# connect.net
KiCad netlist of a schematic drawn in Altium Designer
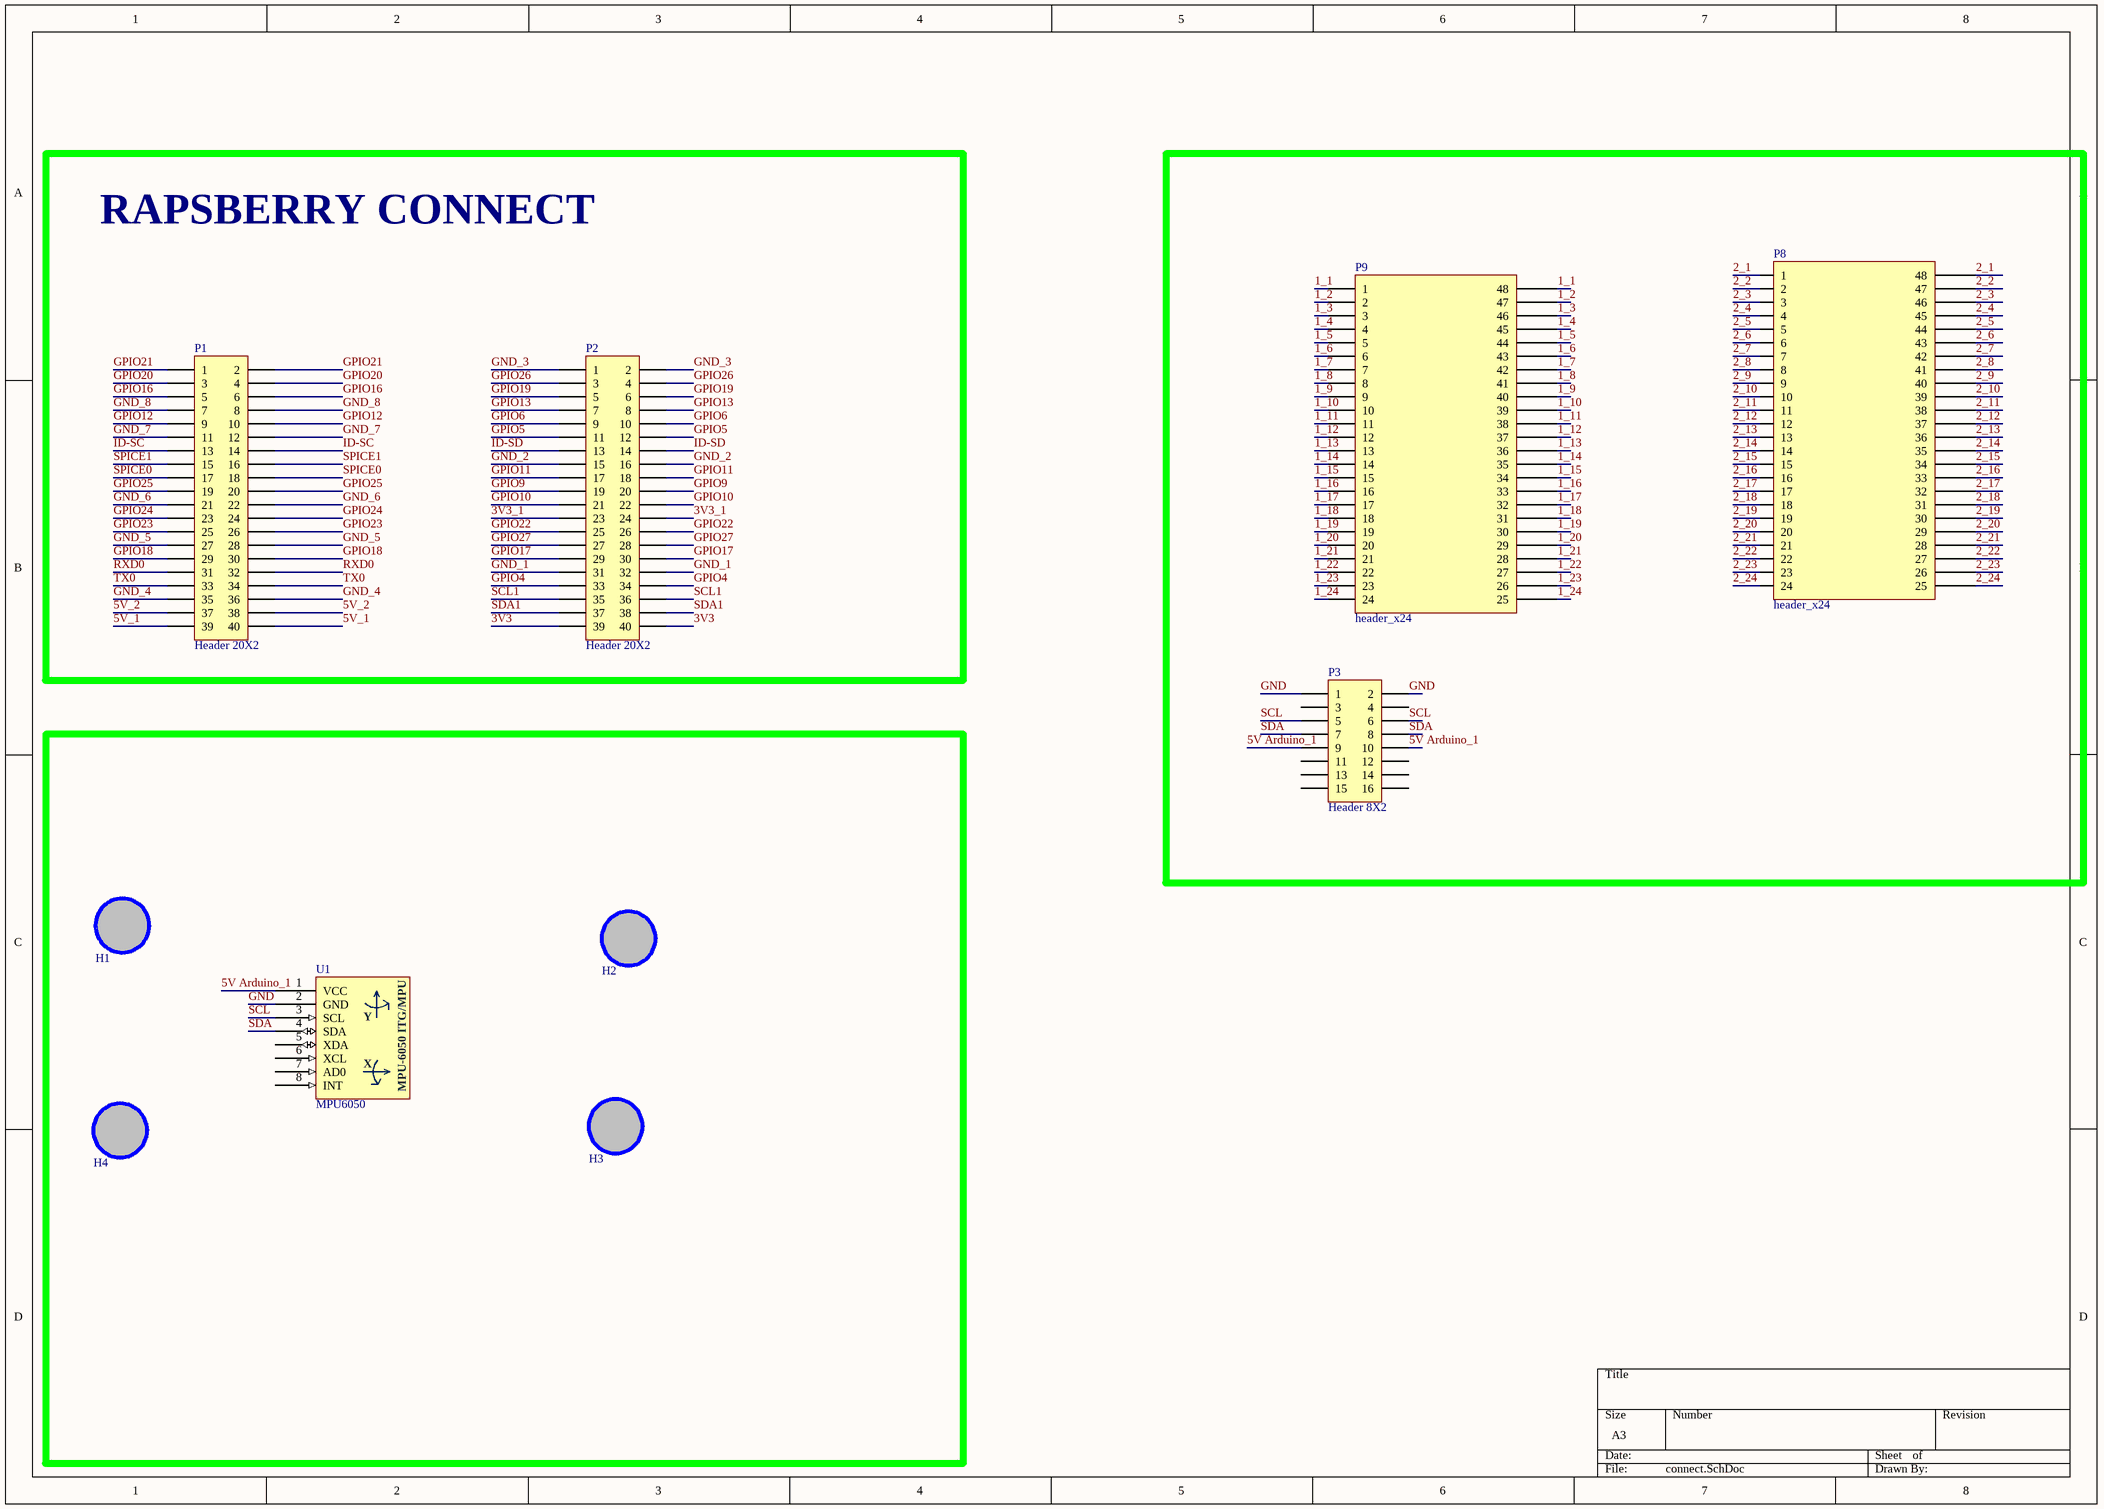
[diagram p0: connect.SchDoc]

(export (version "E")
  (design (tool "Eeschema 10.0.6"))
  (components
    (comp (ref "H1")
      (value "Hole")
      (footprint "LO KHOAN 3MM")
      (description "Hole 3mm")
      (libsource (lib "Board_C24") (part "Hole"))
    )
    (comp (ref "H2")
      (value "Hole")
      (footprint "LO KHOAN 3MM")
      (description "Hole 3mm")
      (libsource (lib "Board_C24") (part "Hole"))
    )
    (comp (ref "H3")
      (value "Hole")
      (footprint "LO KHOAN 3MM")
      (description "Hole 3mm")
      (libsource (lib "Board_C24") (part "Hole"))
    )
    (comp (ref "H4")
      (value "Hole")
      (footprint "LO KHOAN 3MM")
      (description "Hole 3mm")
      (libsource (lib "Board_C24") (part "Hole"))
    )
    (comp (ref "P1")
      (value "Header 20X2")
      (footprint "MY_2X20")
      (description "Header, 40-Pin, Dual row")
      (fields (field (name "ASID PART NUMBER") "Header 20X2-AS"))
      (libsource (lib "Mylib+Rev+4") (part "Header 20X2"))
    )
    (comp (ref "P2")
      (value "Header 20X2")
      (footprint "MY_2X20")
      (description "Header, 40-Pin, Dual row")
      (fields (field (name "ASID PART NUMBER") "Header 20X2-AS"))
      (libsource (lib "Mylib+Rev+4") (part "Header 20X2"))
    )
    (comp (ref "P3")
      (value "Header 8X2")
      (footprint "HDR/Header/16/DL")
      (description "Header, 8-Pin, Dual row")
      (libsource (lib "connectors") (part "Header 8X2"))
    )
    (comp (ref "P8")
      (value "header_x24")
      (footprint "header_x24")
      (libsource (lib "Integrated_Library1") (part "header_x24"))
    )
    (comp (ref "P9")
      (value "header_x24")
      (footprint "header_x24")
      (libsource (lib "Integrated_Library1") (part "header_x24"))
    )
    (comp (ref "U1")
      (value "MPU6050")
      (footprint "MPU-6050")
      (fields (field (name "MFR") "DFRobot") (field (name "UTILIZED IC / PART") "MPU-6050"))
      (libsource (lib "Board_C24") (part "MPU6050"))
    )
  )
  (nets
    (net (code "1") (name "/1_1") (class "Default")
      (node (ref "P9") (pin "1") (pinfunction "1_1") (pintype "passive"))
      (node (ref "P9") (pin "48") (pinfunction "48_48") (pintype "passive"))
    )
    (net (code "2") (name "/1_2") (class "Default")
      (node (ref "P9") (pin "2") (pinfunction "2_2") (pintype "passive"))
      (node (ref "P9") (pin "47") (pinfunction "47_47") (pintype "passive"))
    )
    (net (code "3") (name "/1_3") (class "Default")
      (node (ref "P9") (pin "3") (pinfunction "3_3") (pintype "passive"))
      (node (ref "P9") (pin "46") (pinfunction "46_46") (pintype "passive"))
    )
    (net (code "4") (name "/1_4") (class "Default")
      (node (ref "P9") (pin "4") (pinfunction "4_4") (pintype "passive"))
      (node (ref "P9") (pin "45") (pinfunction "45_45") (pintype "passive"))
    )
    (net (code "5") (name "/1_5") (class "Default")
      (node (ref "P9") (pin "44") (pinfunction "44_44") (pintype "passive"))
      (node (ref "P9") (pin "5") (pinfunction "5_5") (pintype "passive"))
    )
    (net (code "6") (name "/1_6") (class "Default")
      (node (ref "P9") (pin "43") (pinfunction "43_43") (pintype "passive"))
      (node (ref "P9") (pin "6") (pinfunction "6_6") (pintype "passive"))
    )
    (net (code "7") (name "/1_7") (class "Default")
      (node (ref "P9") (pin "42") (pinfunction "42_42") (pintype "passive"))
      (node (ref "P9") (pin "7") (pinfunction "7_7") (pintype "passive"))
    )
    (net (code "8") (name "/1_8") (class "Default")
      (node (ref "P9") (pin "41") (pinfunction "41_41") (pintype "passive"))
      (node (ref "P9") (pin "8") (pinfunction "8_8") (pintype "passive"))
    )
    (net (code "9") (name "/1_9") (class "Default")
      (node (ref "P9") (pin "40") (pinfunction "40_40") (pintype "passive"))
      (node (ref "P9") (pin "9") (pinfunction "9_9") (pintype "passive"))
    )
    (net (code "10") (name "/1_10") (class "Default")
      (node (ref "P9") (pin "10") (pinfunction "10_10") (pintype "passive"))
      (node (ref "P9") (pin "39") (pinfunction "39_39") (pintype "passive"))
    )
    (net (code "11") (name "/1_11") (class "Default")
      (node (ref "P9") (pin "11") (pinfunction "11_11") (pintype "passive"))
      (node (ref "P9") (pin "38") (pinfunction "38_38") (pintype "passive"))
    )
    (net (code "12") (name "/1_12") (class "Default")
      (node (ref "P9") (pin "12") (pinfunction "12_12") (pintype "passive"))
      (node (ref "P9") (pin "37") (pinfunction "37_37") (pintype "passive"))
    )
    (net (code "13") (name "/1_13") (class "Default")
      (node (ref "P9") (pin "13") (pinfunction "13_13") (pintype "passive"))
      (node (ref "P9") (pin "36") (pinfunction "36_36") (pintype "passive"))
    )
    (net (code "14") (name "/1_14") (class "Default")
      (node (ref "P9") (pin "14") (pinfunction "14_14") (pintype "passive"))
      (node (ref "P9") (pin "35") (pinfunction "35_35") (pintype "passive"))
    )
    (net (code "15") (name "/1_15") (class "Default")
      (node (ref "P9") (pin "15") (pinfunction "15_15") (pintype "passive"))
      (node (ref "P9") (pin "34") (pinfunction "34_34") (pintype "passive"))
    )
    (net (code "16") (name "/1_16") (class "Default")
      (node (ref "P9") (pin "16") (pinfunction "16_16") (pintype "passive"))
      (node (ref "P9") (pin "33") (pinfunction "33_33") (pintype "passive"))
    )
    (net (code "17") (name "/1_17") (class "Default")
      (node (ref "P9") (pin "17") (pinfunction "17_17") (pintype "passive"))
      (node (ref "P9") (pin "32") (pinfunction "32_32") (pintype "passive"))
    )
    (net (code "18") (name "/1_18") (class "Default")
      (node (ref "P9") (pin "18") (pinfunction "18_18") (pintype "passive"))
      (node (ref "P9") (pin "31") (pinfunction "31_31") (pintype "passive"))
    )
    (net (code "19") (name "/1_19") (class "Default")
      (node (ref "P9") (pin "19") (pinfunction "19_19") (pintype "passive"))
      (node (ref "P9") (pin "30") (pinfunction "30_30") (pintype "passive"))
    )
    (net (code "20") (name "/1_20") (class "Default")
      (node (ref "P9") (pin "20") (pinfunction "20_20") (pintype "passive"))
      (node (ref "P9") (pin "29") (pinfunction "29_29") (pintype "passive"))
    )
    (net (code "21") (name "/1_21") (class "Default")
      (node (ref "P9") (pin "21") (pinfunction "21_21") (pintype "passive"))
      (node (ref "P9") (pin "28") (pinfunction "28_28") (pintype "passive"))
    )
    (net (code "22") (name "/1_22") (class "Default")
      (node (ref "P9") (pin "22") (pinfunction "22_22") (pintype "passive"))
      (node (ref "P9") (pin "27") (pinfunction "27_27") (pintype "passive"))
    )
    (net (code "23") (name "/1_23") (class "Default")
      (node (ref "P9") (pin "23") (pinfunction "23_23") (pintype "passive"))
      (node (ref "P9") (pin "26") (pinfunction "26_26") (pintype "passive"))
    )
    (net (code "24") (name "/1_24") (class "Default")
      (node (ref "P9") (pin "24") (pinfunction "24_24") (pintype "passive"))
      (node (ref "P9") (pin "25") (pinfunction "25_25") (pintype "passive"))
    )
    (net (code "25") (name "/2_1") (class "Default")
      (node (ref "P8") (pin "1") (pinfunction "1_1") (pintype "passive"))
      (node (ref "P8") (pin "48") (pinfunction "48_48") (pintype "passive"))
    )
    (net (code "26") (name "/2_2") (class "Default")
      (node (ref "P8") (pin "2") (pinfunction "2_2") (pintype "passive"))
      (node (ref "P8") (pin "47") (pinfunction "47_47") (pintype "passive"))
    )
    (net (code "27") (name "/2_3") (class "Default")
      (node (ref "P8") (pin "3") (pinfunction "3_3") (pintype "passive"))
      (node (ref "P8") (pin "46") (pinfunction "46_46") (pintype "passive"))
    )
    (net (code "28") (name "/2_4") (class "Default")
      (node (ref "P8") (pin "4") (pinfunction "4_4") (pintype "passive"))
      (node (ref "P8") (pin "45") (pinfunction "45_45") (pintype "passive"))
    )
    (net (code "29") (name "/2_5") (class "Default")
      (node (ref "P8") (pin "44") (pinfunction "44_44") (pintype "passive"))
      (node (ref "P8") (pin "5") (pinfunction "5_5") (pintype "passive"))
    )
    (net (code "30") (name "/2_6") (class "Default")
      (node (ref "P8") (pin "43") (pinfunction "43_43") (pintype "passive"))
      (node (ref "P8") (pin "6") (pinfunction "6_6") (pintype "passive"))
    )
    (net (code "31") (name "/2_7") (class "Default")
      (node (ref "P8") (pin "42") (pinfunction "42_42") (pintype "passive"))
      (node (ref "P8") (pin "7") (pinfunction "7_7") (pintype "passive"))
    )
    (net (code "32") (name "/2_8") (class "Default")
      (node (ref "P8") (pin "41") (pinfunction "41_41") (pintype "passive"))
      (node (ref "P8") (pin "8") (pinfunction "8_8") (pintype "passive"))
    )
    (net (code "33") (name "/2_9") (class "Default")
      (node (ref "P8") (pin "40") (pinfunction "40_40") (pintype "passive"))
      (node (ref "P8") (pin "9") (pinfunction "9_9") (pintype "passive"))
    )
    (net (code "34") (name "/2_10") (class "Default")
      (node (ref "P8") (pin "10") (pinfunction "10_10") (pintype "passive"))
      (node (ref "P8") (pin "39") (pinfunction "39_39") (pintype "passive"))
    )
    (net (code "35") (name "/2_11") (class "Default")
      (node (ref "P8") (pin "11") (pinfunction "11_11") (pintype "passive"))
      (node (ref "P8") (pin "38") (pinfunction "38_38") (pintype "passive"))
    )
    (net (code "36") (name "/2_12") (class "Default")
      (node (ref "P8") (pin "12") (pinfunction "12_12") (pintype "passive"))
      (node (ref "P8") (pin "37") (pinfunction "37_37") (pintype "passive"))
    )
    (net (code "37") (name "/2_13") (class "Default")
      (node (ref "P8") (pin "13") (pinfunction "13_13") (pintype "passive"))
      (node (ref "P8") (pin "36") (pinfunction "36_36") (pintype "passive"))
    )
    (net (code "38") (name "/2_14") (class "Default")
      (node (ref "P8") (pin "14") (pinfunction "14_14") (pintype "passive"))
      (node (ref "P8") (pin "35") (pinfunction "35_35") (pintype "passive"))
    )
    (net (code "39") (name "/2_15") (class "Default")
      (node (ref "P8") (pin "15") (pinfunction "15_15") (pintype "passive"))
      (node (ref "P8") (pin "34") (pinfunction "34_34") (pintype "passive"))
    )
    (net (code "40") (name "/2_16") (class "Default")
      (node (ref "P8") (pin "16") (pinfunction "16_16") (pintype "passive"))
      (node (ref "P8") (pin "33") (pinfunction "33_33") (pintype "passive"))
    )
    (net (code "41") (name "/2_17") (class "Default")
      (node (ref "P8") (pin "17") (pinfunction "17_17") (pintype "passive"))
      (node (ref "P8") (pin "32") (pinfunction "32_32") (pintype "passive"))
    )
    (net (code "42") (name "/2_18") (class "Default")
      (node (ref "P8") (pin "18") (pinfunction "18_18") (pintype "passive"))
      (node (ref "P8") (pin "31") (pinfunction "31_31") (pintype "passive"))
    )
    (net (code "43") (name "/2_19") (class "Default")
      (node (ref "P8") (pin "19") (pinfunction "19_19") (pintype "passive"))
      (node (ref "P8") (pin "30") (pinfunction "30_30") (pintype "passive"))
    )
    (net (code "44") (name "/2_20") (class "Default")
      (node (ref "P8") (pin "20") (pinfunction "20_20") (pintype "passive"))
      (node (ref "P8") (pin "29") (pinfunction "29_29") (pintype "passive"))
    )
    (net (code "45") (name "/2_21") (class "Default")
      (node (ref "P8") (pin "21") (pinfunction "21_21") (pintype "passive"))
      (node (ref "P8") (pin "28") (pinfunction "28_28") (pintype "passive"))
    )
    (net (code "46") (name "/2_22") (class "Default")
      (node (ref "P8") (pin "22") (pinfunction "22_22") (pintype "passive"))
      (node (ref "P8") (pin "27") (pinfunction "27_27") (pintype "passive"))
    )
    (net (code "47") (name "/2_23") (class "Default")
      (node (ref "P8") (pin "23") (pinfunction "23_23") (pintype "passive"))
      (node (ref "P8") (pin "26") (pinfunction "26_26") (pintype "passive"))
    )
    (net (code "48") (name "/2_24") (class "Default")
      (node (ref "P8") (pin "24") (pinfunction "24_24") (pintype "passive"))
      (node (ref "P8") (pin "25") (pinfunction "25_25") (pintype "passive"))
    )
    (net (code "49") (name "/3V3") (class "Default")
      (node (ref "P2") (pin "39") (pinfunction "39_39") (pintype "passive"))
      (node (ref "P2") (pin "40") (pinfunction "40_40") (pintype "passive"))
    )
    (net (code "50") (name "/3V3_1") (class "Default")
      (node (ref "P2") (pin "23") (pinfunction "23_23") (pintype "passive"))
      (node (ref "P2") (pin "24") (pinfunction "24_24") (pintype "passive"))
    )
    (net (code "51") (name "/5V Arduino_1") (class "Default")
      (node (ref "P3") (pin "10") (pinfunction "10_10") (pintype "passive"))
      (node (ref "P3") (pin "9") (pinfunction "9_9") (pintype "passive"))
      (node (ref "U1") (pin "1") (pinfunction "VCC_1") (pintype "power_in"))
    )
    (net (code "52") (name "/5V_1") (class "Default")
      (node (ref "P1") (pin "39") (pinfunction "39_39") (pintype "passive"))
      (node (ref "P1") (pin "40") (pinfunction "40_40") (pintype "passive"))
    )
    (net (code "53") (name "/5V_2") (class "Default")
      (node (ref "P1") (pin "37") (pinfunction "37_37") (pintype "passive"))
      (node (ref "P1") (pin "38") (pinfunction "38_38") (pintype "passive"))
    )
    (net (code "54") (name "/GND") (class "Default")
      (node (ref "P3") (pin "1") (pinfunction "1_1") (pintype "passive"))
      (node (ref "P3") (pin "2") (pinfunction "2_2") (pintype "passive"))
      (node (ref "U1") (pin "2") (pinfunction "GND_2") (pintype "power_in"))
    )
    (net (code "55") (name "/GND_1") (class "Default")
      (node (ref "P2") (pin "31") (pinfunction "31_31") (pintype "passive"))
      (node (ref "P2") (pin "32") (pinfunction "32_32") (pintype "passive"))
    )
    (net (code "56") (name "/GND_2") (class "Default")
      (node (ref "P2") (pin "15") (pinfunction "15_15") (pintype "passive"))
      (node (ref "P2") (pin "16") (pinfunction "16_16") (pintype "passive"))
    )
    (net (code "57") (name "/GND_3") (class "Default")
      (node (ref "P2") (pin "1") (pinfunction "1_1") (pintype "passive"))
      (node (ref "P2") (pin "2") (pinfunction "2_2") (pintype "passive"))
    )
    (net (code "58") (name "/GND_4") (class "Default")
      (node (ref "P1") (pin "35") (pinfunction "35_35") (pintype "passive"))
      (node (ref "P1") (pin "36") (pinfunction "36_36") (pintype "passive"))
    )
    (net (code "59") (name "/GND_5") (class "Default")
      (node (ref "P1") (pin "27") (pinfunction "27_27") (pintype "passive"))
      (node (ref "P1") (pin "28") (pinfunction "28_28") (pintype "passive"))
    )
    (net (code "60") (name "/GND_6") (class "Default")
      (node (ref "P1") (pin "21") (pinfunction "21_21") (pintype "passive"))
      (node (ref "P1") (pin "22") (pinfunction "22_22") (pintype "passive"))
    )
    (net (code "61") (name "/GND_7") (class "Default")
      (node (ref "P1") (pin "11") (pinfunction "11_11") (pintype "passive"))
      (node (ref "P1") (pin "12") (pinfunction "12_12") (pintype "passive"))
    )
    (net (code "62") (name "/GND_8") (class "Default")
      (node (ref "P1") (pin "7") (pinfunction "7_7") (pintype "passive"))
      (node (ref "P1") (pin "8") (pinfunction "8_8") (pintype "passive"))
    )
    (net (code "63") (name "/GPIO4") (class "Default")
      (node (ref "P2") (pin "33") (pinfunction "33_33") (pintype "passive"))
      (node (ref "P2") (pin "34") (pinfunction "34_34") (pintype "passive"))
    )
    (net (code "64") (name "/GPIO5") (class "Default")
      (node (ref "P2") (pin "11") (pinfunction "11_11") (pintype "passive"))
      (node (ref "P2") (pin "12") (pinfunction "12_12") (pintype "passive"))
    )
    (net (code "65") (name "/GPIO6") (class "Default")
      (node (ref "P2") (pin "10") (pinfunction "10_10") (pintype "passive"))
      (node (ref "P2") (pin "9") (pinfunction "9_9") (pintype "passive"))
    )
    (net (code "66") (name "/GPIO9") (class "Default")
      (node (ref "P2") (pin "19") (pinfunction "19_19") (pintype "passive"))
      (node (ref "P2") (pin "20") (pinfunction "20_20") (pintype "passive"))
    )
    (net (code "67") (name "/GPIO10") (class "Default")
      (node (ref "P2") (pin "21") (pinfunction "21_21") (pintype "passive"))
      (node (ref "P2") (pin "22") (pinfunction "22_22") (pintype "passive"))
    )
    (net (code "68") (name "/GPIO11") (class "Default")
      (node (ref "P2") (pin "17") (pinfunction "17_17") (pintype "passive"))
      (node (ref "P2") (pin "18") (pinfunction "18_18") (pintype "passive"))
    )
    (net (code "69") (name "/GPIO12") (class "Default")
      (node (ref "P1") (pin "10") (pinfunction "10_10") (pintype "passive"))
      (node (ref "P1") (pin "9") (pinfunction "9_9") (pintype "passive"))
    )
    (net (code "70") (name "/GPIO13") (class "Default")
      (node (ref "P2") (pin "7") (pinfunction "7_7") (pintype "passive"))
      (node (ref "P2") (pin "8") (pinfunction "8_8") (pintype "passive"))
    )
    (net (code "71") (name "/GPIO16") (class "Default")
      (node (ref "P1") (pin "5") (pinfunction "5_5") (pintype "passive"))
      (node (ref "P1") (pin "6") (pinfunction "6_6") (pintype "passive"))
    )
    (net (code "72") (name "/GPIO17") (class "Default")
      (node (ref "P2") (pin "29") (pinfunction "29_29") (pintype "passive"))
      (node (ref "P2") (pin "30") (pinfunction "30_30") (pintype "passive"))
    )
    (net (code "73") (name "/GPIO18") (class "Default")
      (node (ref "P1") (pin "29") (pinfunction "29_29") (pintype "passive"))
      (node (ref "P1") (pin "30") (pinfunction "30_30") (pintype "passive"))
    )
    (net (code "74") (name "/GPIO19") (class "Default")
      (node (ref "P2") (pin "5") (pinfunction "5_5") (pintype "passive"))
      (node (ref "P2") (pin "6") (pinfunction "6_6") (pintype "passive"))
    )
    (net (code "75") (name "/GPIO20") (class "Default")
      (node (ref "P1") (pin "3") (pinfunction "3_3") (pintype "passive"))
      (node (ref "P1") (pin "4") (pinfunction "4_4") (pintype "passive"))
    )
    (net (code "76") (name "/GPIO21") (class "Default")
      (node (ref "P1") (pin "1") (pinfunction "1_1") (pintype "passive"))
      (node (ref "P1") (pin "2") (pinfunction "2_2") (pintype "passive"))
    )
    (net (code "77") (name "/GPIO22") (class "Default")
      (node (ref "P2") (pin "25") (pinfunction "25_25") (pintype "passive"))
      (node (ref "P2") (pin "26") (pinfunction "26_26") (pintype "passive"))
    )
    (net (code "78") (name "/GPIO23") (class "Default")
      (node (ref "P1") (pin "25") (pinfunction "25_25") (pintype "passive"))
      (node (ref "P1") (pin "26") (pinfunction "26_26") (pintype "passive"))
    )
    (net (code "79") (name "/GPIO24") (class "Default")
      (node (ref "P1") (pin "23") (pinfunction "23_23") (pintype "passive"))
      (node (ref "P1") (pin "24") (pinfunction "24_24") (pintype "passive"))
    )
    (net (code "80") (name "/GPIO25") (class "Default")
      (node (ref "P1") (pin "19") (pinfunction "19_19") (pintype "passive"))
      (node (ref "P1") (pin "20") (pinfunction "20_20") (pintype "passive"))
    )
    (net (code "81") (name "/GPIO26") (class "Default")
      (node (ref "P2") (pin "3") (pinfunction "3_3") (pintype "passive"))
      (node (ref "P2") (pin "4") (pinfunction "4_4") (pintype "passive"))
    )
    (net (code "82") (name "/GPIO27") (class "Default")
      (node (ref "P2") (pin "27") (pinfunction "27_27") (pintype "passive"))
      (node (ref "P2") (pin "28") (pinfunction "28_28") (pintype "passive"))
    )
    (net (code "83") (name "/ID-SC") (class "Default")
      (node (ref "P1") (pin "13") (pinfunction "13_13") (pintype "passive"))
      (node (ref "P1") (pin "14") (pinfunction "14_14") (pintype "passive"))
    )
    (net (code "84") (name "/ID-SD") (class "Default")
      (node (ref "P2") (pin "13") (pinfunction "13_13") (pintype "passive"))
      (node (ref "P2") (pin "14") (pinfunction "14_14") (pintype "passive"))
    )
    (net (code "85") (name "/RXD0") (class "Default")
      (node (ref "P1") (pin "31") (pinfunction "31_31") (pintype "passive"))
      (node (ref "P1") (pin "32") (pinfunction "32_32") (pintype "passive"))
    )
    (net (code "86") (name "/SCL") (class "Default")
      (node (ref "P3") (pin "5") (pinfunction "5_5") (pintype "passive"))
      (node (ref "P3") (pin "6") (pinfunction "6_6") (pintype "passive"))
      (node (ref "U1") (pin "3") (pinfunction "SCL_3") (pintype "input"))
    )
    (net (code "87") (name "/SCL1") (class "Default")
      (node (ref "P2") (pin "35") (pinfunction "35_35") (pintype "passive"))
      (node (ref "P2") (pin "36") (pinfunction "36_36") (pintype "passive"))
    )
    (net (code "88") (name "/SDA") (class "Default")
      (node (ref "P3") (pin "7") (pinfunction "7_7") (pintype "passive"))
      (node (ref "P3") (pin "8") (pinfunction "8_8") (pintype "passive"))
      (node (ref "U1") (pin "4") (pinfunction "SDA_4") (pintype "bidirectional"))
    )
    (net (code "89") (name "/SDA1") (class "Default")
      (node (ref "P2") (pin "37") (pinfunction "37_37") (pintype "passive"))
      (node (ref "P2") (pin "38") (pinfunction "38_38") (pintype "passive"))
    )
    (net (code "90") (name "/SPICE0") (class "Default")
      (node (ref "P1") (pin "17") (pinfunction "17_17") (pintype "passive"))
      (node (ref "P1") (pin "18") (pinfunction "18_18") (pintype "passive"))
    )
    (net (code "91") (name "/SPICE1") (class "Default")
      (node (ref "P1") (pin "15") (pinfunction "15_15") (pintype "passive"))
      (node (ref "P1") (pin "16") (pinfunction "16_16") (pintype "passive"))
    )
    (net (code "92") (name "/TX0") (class "Default")
      (node (ref "P1") (pin "33") (pinfunction "33_33") (pintype "passive"))
      (node (ref "P1") (pin "34") (pinfunction "34_34") (pintype "passive"))
    )
    (net (code "93") (name "unconnected-(H1-Pad1)") (class "Default")
      (node (ref "H1") (pin "1") (pinfunction "1_1") (pintype "passive"))
    )
    (net (code "94") (name "unconnected-(H2-Pad1)") (class "Default")
      (node (ref "H2") (pin "1") (pinfunction "1_1") (pintype "passive"))
    )
    (net (code "95") (name "unconnected-(H3-Pad1)") (class "Default")
      (node (ref "H3") (pin "1") (pinfunction "1_1") (pintype "passive"))
    )
    (net (code "96") (name "unconnected-(H4-Pad1)") (class "Default")
      (node (ref "H4") (pin "1") (pinfunction "1_1") (pintype "passive"))
    )
    (net (code "97") (name "unconnected-(P3-Pad3)") (class "Default")
      (node (ref "P3") (pin "3") (pinfunction "3_3") (pintype "passive"))
    )
    (net (code "98") (name "unconnected-(P3-Pad4)") (class "Default")
      (node (ref "P3") (pin "4") (pinfunction "4_4") (pintype "passive"))
    )
    (net (code "99") (name "unconnected-(P3-Pad11)") (class "Default")
      (node (ref "P3") (pin "11") (pinfunction "11_11") (pintype "passive"))
    )
    (net (code "100") (name "unconnected-(P3-Pad12)") (class "Default")
      (node (ref "P3") (pin "12") (pinfunction "12_12") (pintype "passive"))
    )
    (net (code "101") (name "unconnected-(P3-Pad13)") (class "Default")
      (node (ref "P3") (pin "13") (pinfunction "13_13") (pintype "passive"))
    )
    (net (code "102") (name "unconnected-(P3-Pad14)") (class "Default")
      (node (ref "P3") (pin "14") (pinfunction "14_14") (pintype "passive"))
    )
    (net (code "103") (name "unconnected-(P3-Pad15)") (class "Default")
      (node (ref "P3") (pin "15") (pinfunction "15_15") (pintype "passive"))
    )
    (net (code "104") (name "unconnected-(P3-Pad16)") (class "Default")
      (node (ref "P3") (pin "16") (pinfunction "16_16") (pintype "passive"))
    )
    (net (code "105") (name "unconnected-(U1-AD0-Pad7)") (class "Default")
      (node (ref "U1") (pin "7") (pinfunction "AD0_7") (pintype "input"))
    )
    (net (code "106") (name "unconnected-(U1-INT-Pad8)") (class "Default")
      (node (ref "U1") (pin "8") (pinfunction "INT_8") (pintype "input"))
    )
    (net (code "107") (name "unconnected-(U1-XCL-Pad6)") (class "Default")
      (node (ref "U1") (pin "6") (pinfunction "XCL_6") (pintype "input"))
    )
    (net (code "108") (name "unconnected-(U1-XDA-Pad5)") (class "Default")
      (node (ref "U1") (pin "5") (pinfunction "XDA_5") (pintype "bidirectional"))
    )
  )
)
